# CCM_0009.net
KiCad netlist of a schematic drawn in EAGLE
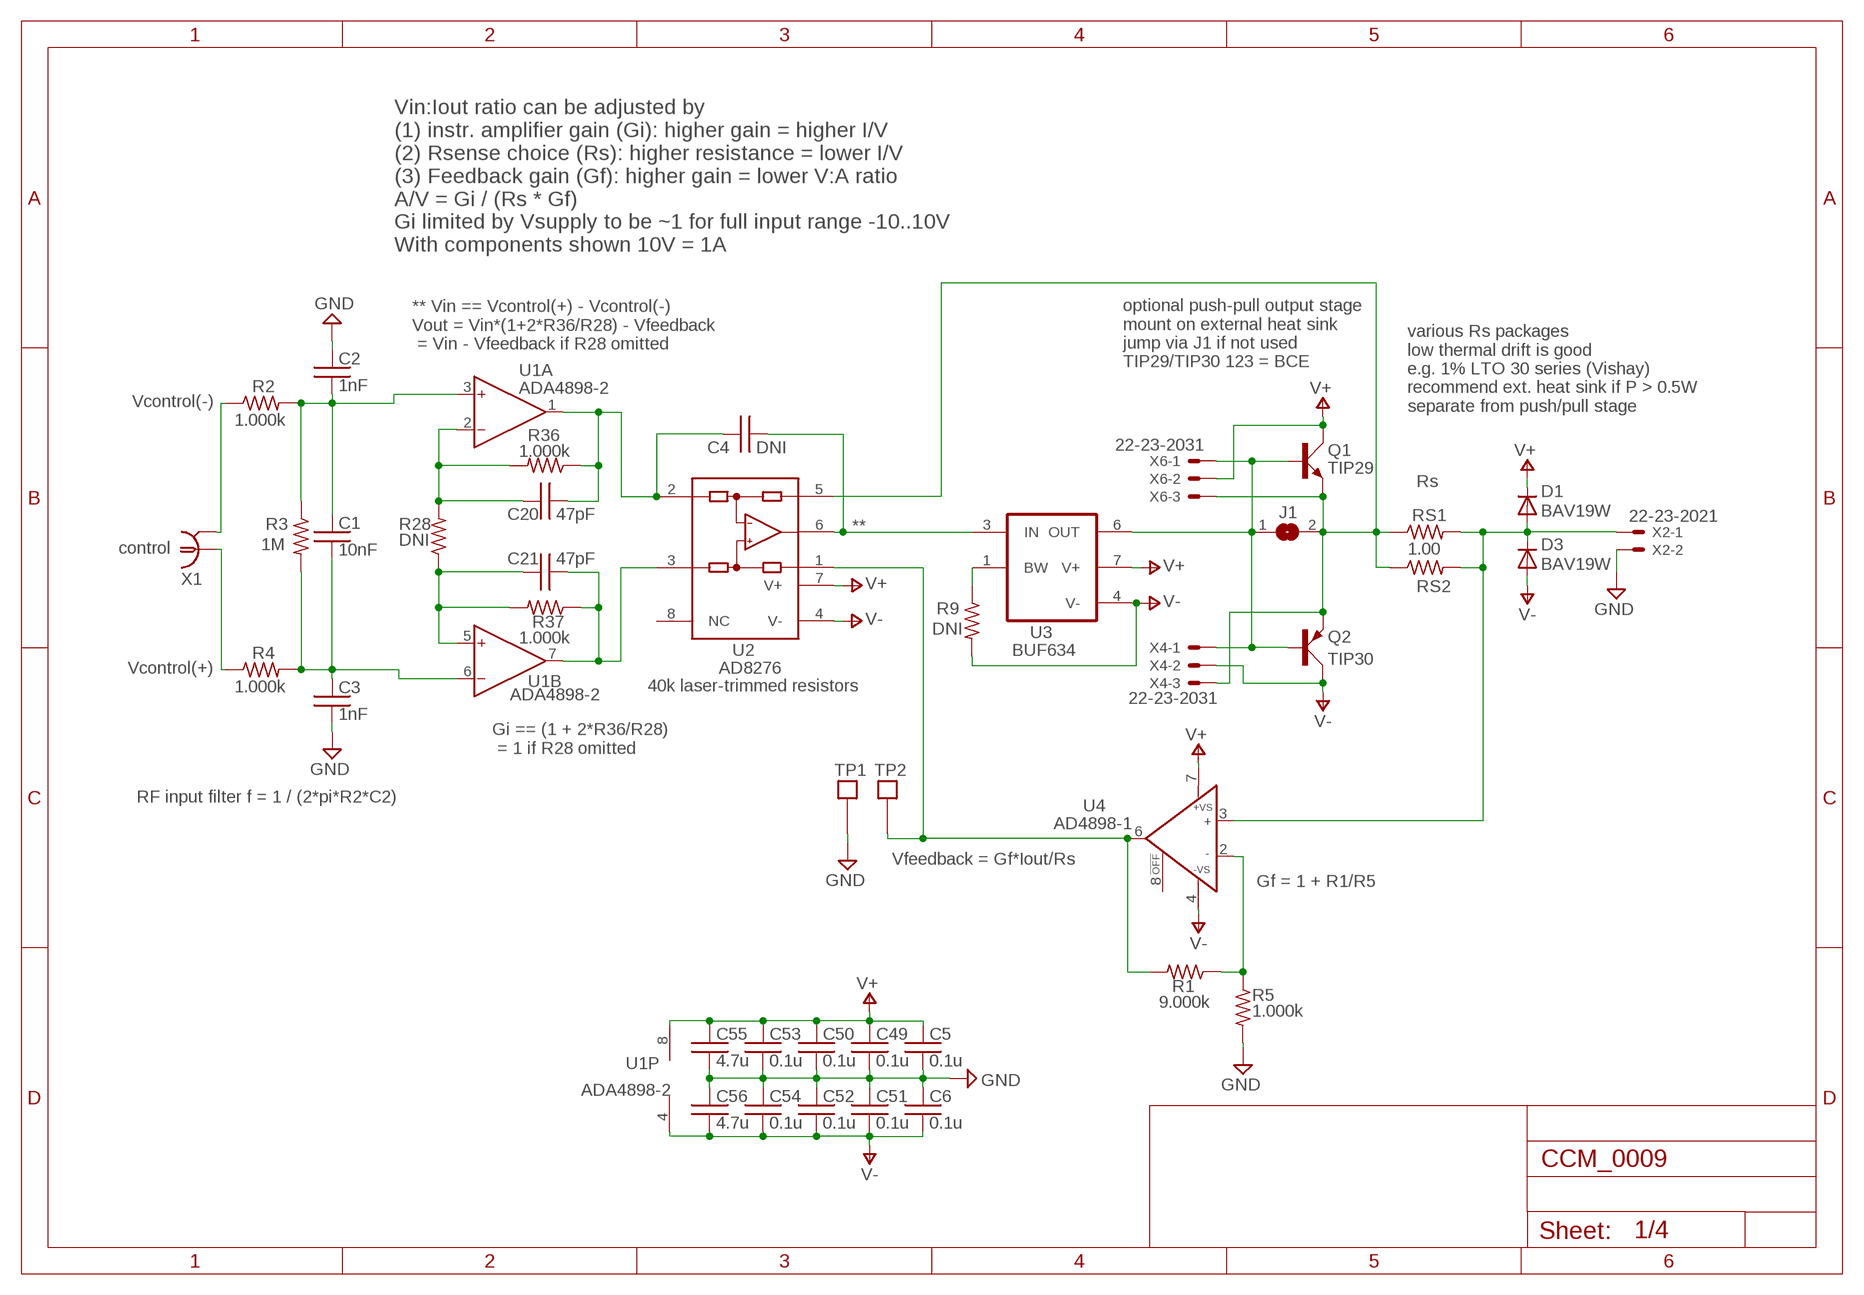
[diagram p0: schematic, sheet 1]
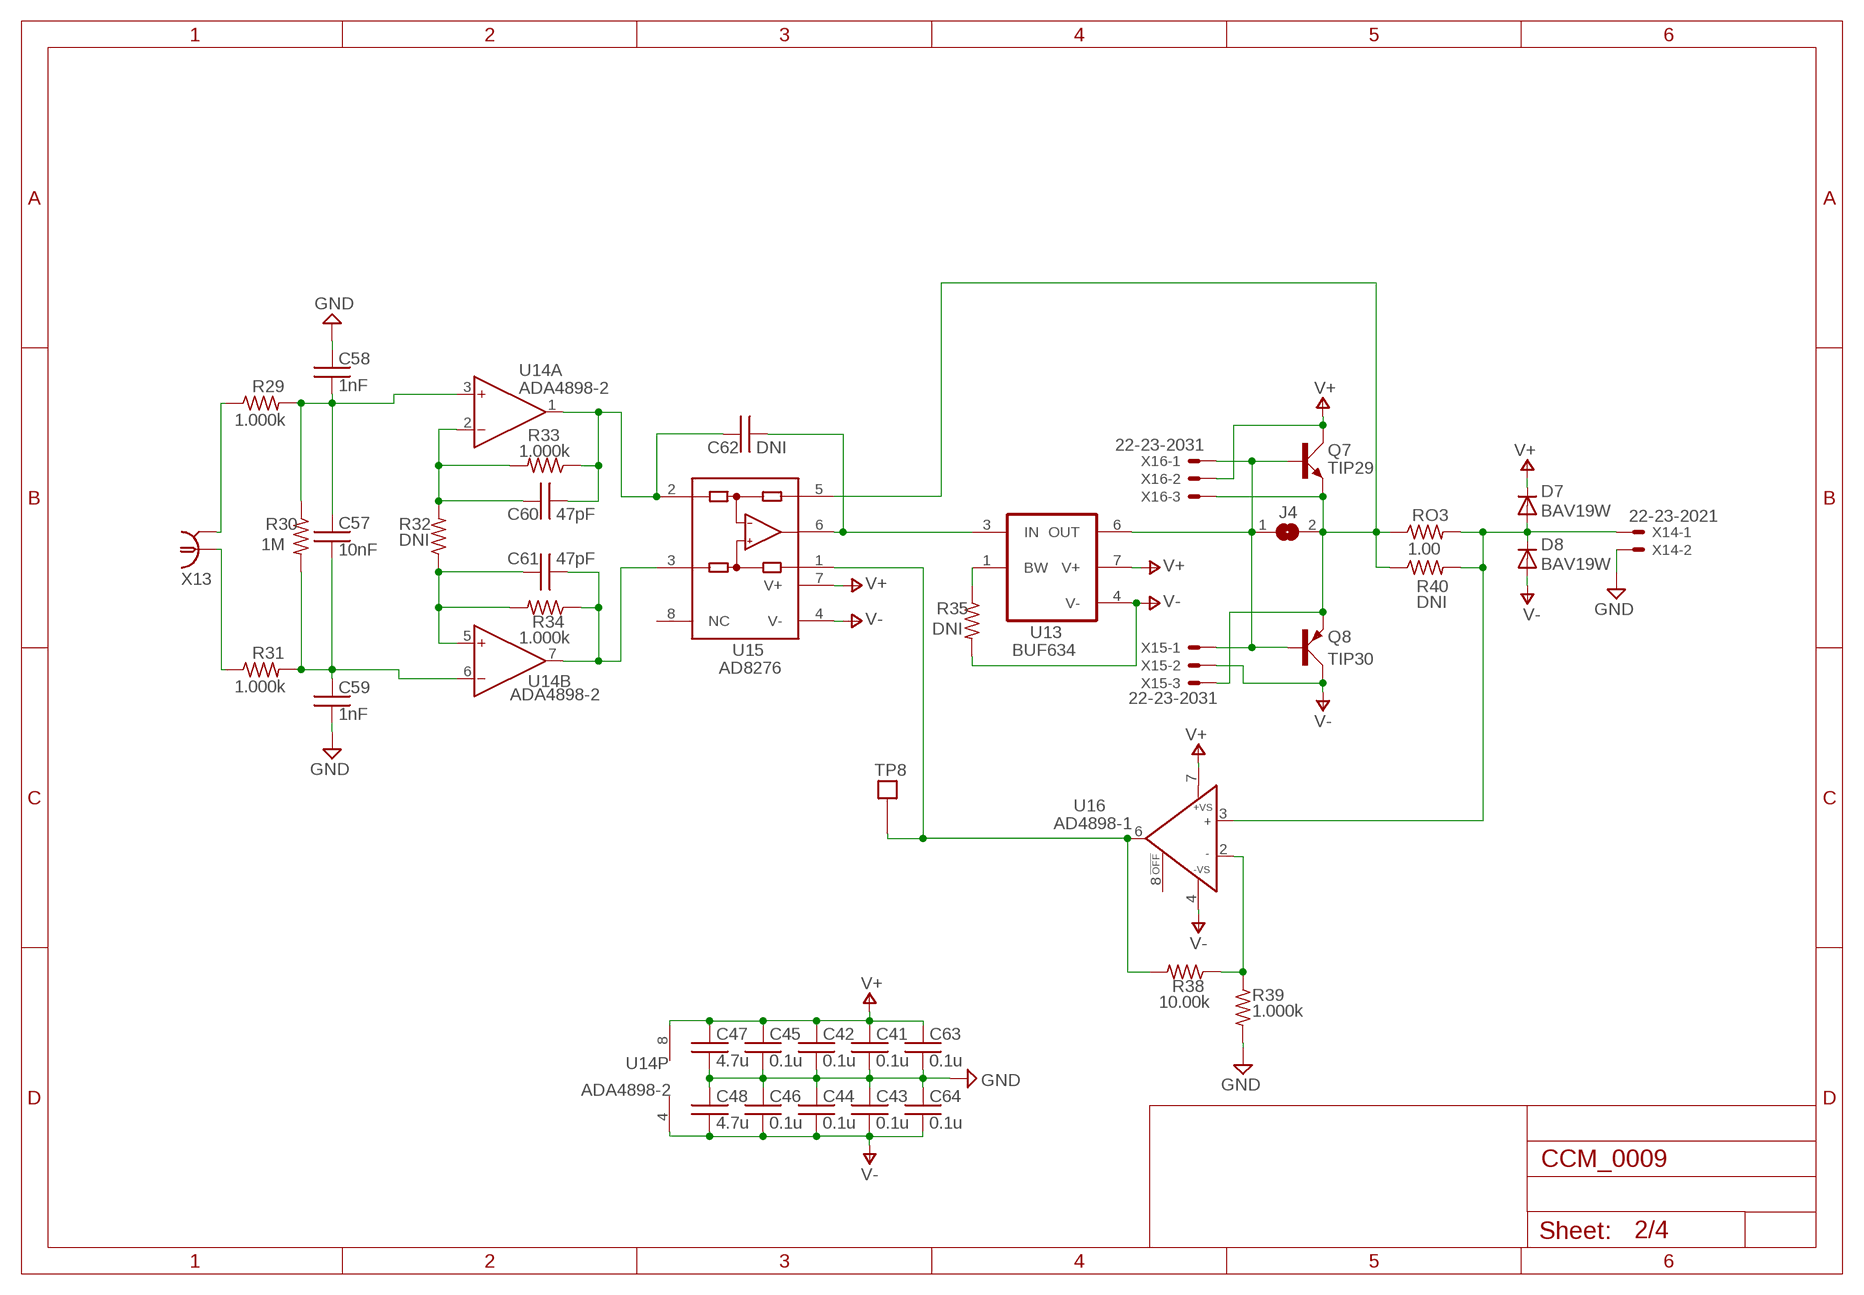
[diagram p1: schematic, sheet 2]
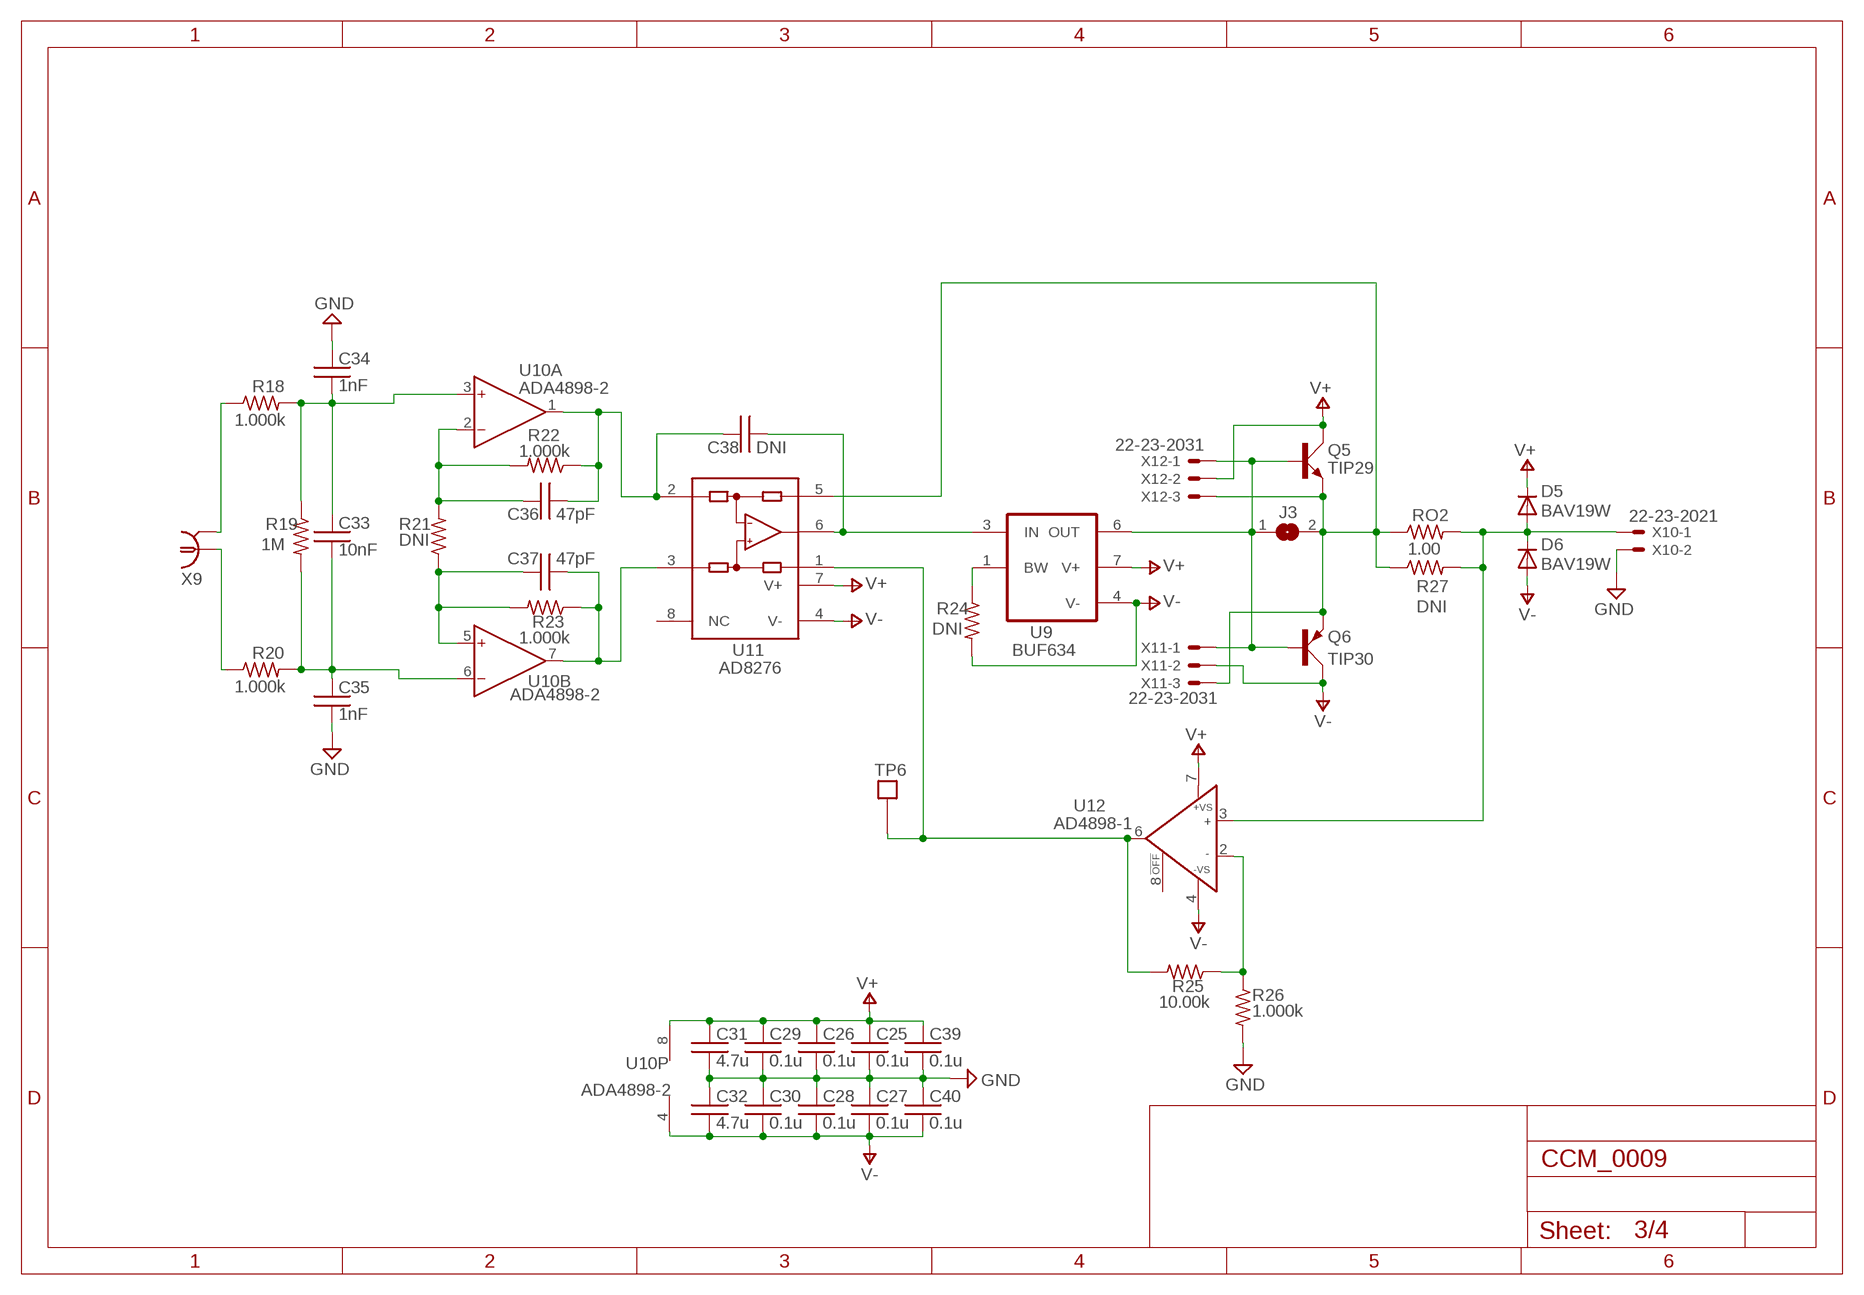
[diagram p2: schematic, sheet 3]
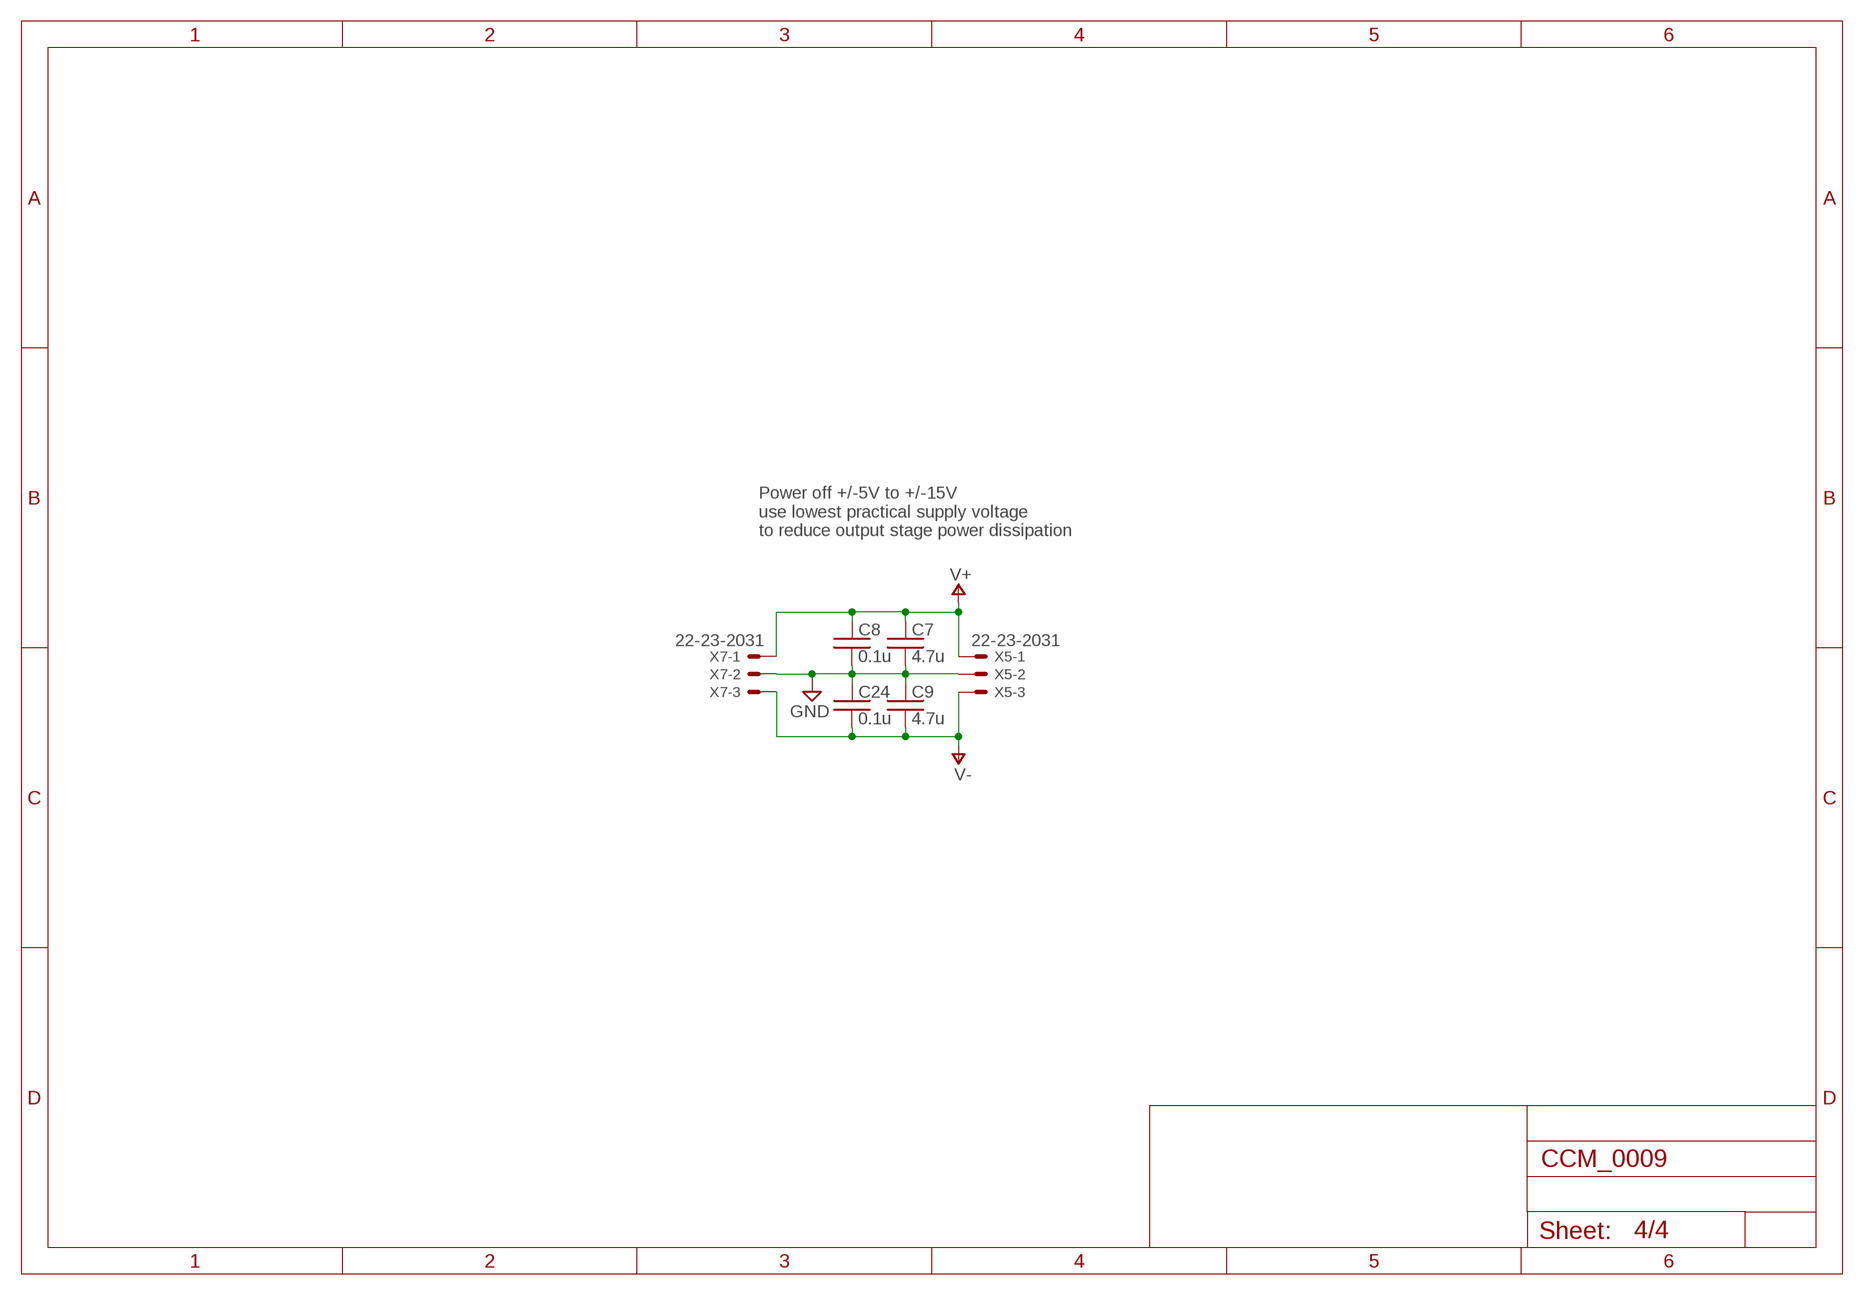
[diagram p3: schematic, sheet 4]

(export (version "E")
  (design (tool "Eeschema 10.0.6"))
  (components
    (comp (ref "C41")
      (value "0.1u")
      (footprint "eagle-import:0603")
      (libsource (lib "eagle-import") (part "C0603"))
    )
    (comp (ref "C42")
      (value "0.1u")
      (footprint "eagle-import:0603")
      (libsource (lib "eagle-import") (part "C0603"))
    )
    (comp (ref "C43")
      (value "0.1u")
      (footprint "eagle-import:0603")
      (libsource (lib "eagle-import") (part "C0603"))
    )
    (comp (ref "C44")
      (value "0.1u")
      (footprint "eagle-import:0603")
      (libsource (lib "eagle-import") (part "C0603"))
    )
    (comp (ref "C45")
      (value "0.1u")
      (footprint "eagle-import:0603")
      (libsource (lib "eagle-import") (part "C0603"))
    )
    (comp (ref "C46")
      (value "0.1u")
      (footprint "eagle-import:0603")
      (libsource (lib "eagle-import") (part "C0603"))
    )
    (comp (ref "C47")
      (value "4.7u")
      (footprint "eagle-import:0603")
      (libsource (lib "eagle-import") (part "C0603"))
    )
    (comp (ref "C48")
      (value "4.7u")
      (footprint "eagle-import:0603")
      (libsource (lib "eagle-import") (part "C0603"))
    )
    (comp (ref "C57")
      (value "10nF")
      (footprint "eagle-import:0603")
      (libsource (lib "eagle-import") (part "C0603"))
    )
    (comp (ref "C58")
      (value "1nF")
      (footprint "eagle-import:0603")
      (libsource (lib "eagle-import") (part "C0603"))
    )
    (comp (ref "C59")
      (value "1nF")
      (footprint "eagle-import:0603")
      (libsource (lib "eagle-import") (part "C0603"))
    )
    (comp (ref "C60")
      (value "47pF")
      (footprint "eagle-import:0603")
      (libsource (lib "eagle-import") (part "C0603"))
    )
    (comp (ref "C61")
      (value "47pF")
      (footprint "eagle-import:0603")
      (libsource (lib "eagle-import") (part "C0603"))
    )
    (comp (ref "C62")
      (value "DNI")
      (footprint "eagle-import:0603")
      (libsource (lib "eagle-import") (part "C0603"))
    )
    (comp (ref "C63")
      (value "0.1u")
      (footprint "eagle-import:0603")
      (libsource (lib "eagle-import") (part "C0603"))
    )
    (comp (ref "C64")
      (value "0.1u")
      (footprint "eagle-import:0603")
      (libsource (lib "eagle-import") (part "C0603"))
    )
    (comp (ref "D7")
      (value "BAV19W")
      (footprint "eagle-import:SOD123")
      (libsource (lib "eagle-import") (part "DIODE-SOD123"))
    )
    (comp (ref "D8")
      (value "BAV19W")
      (footprint "eagle-import:SOD123")
      (libsource (lib "eagle-import") (part "DIODE-SOD123"))
    )
    (comp (ref "J4") (value "SJ") (footprint "eagle-import:SJ") (libsource (lib "eagle-import") (part "SJ")))
    (comp (ref "Q7")
      (value "TIP29")
      (footprint "eagle-import:TO220AV")
      (libsource (lib "eagle-import") (part "TIP41C"))
    )
    (comp (ref "Q8")
      (value "TIP30")
      (footprint "eagle-import:TO220AV")
      (libsource (lib "eagle-import") (part "TIP42C"))
    )
    (comp (ref "R29")
      (value "1.000k")
      (footprint "eagle-import:0603")
      (libsource (lib "eagle-import") (part "R0603"))
    )
    (comp (ref "R30")
      (value "1M")
      (footprint "eagle-import:0603")
      (libsource (lib "eagle-import") (part "R0603"))
    )
    (comp (ref "R31")
      (value "1.000k")
      (footprint "eagle-import:0603")
      (libsource (lib "eagle-import") (part "R0603"))
    )
    (comp (ref "R32")
      (value "DNI")
      (footprint "eagle-import:0603")
      (libsource (lib "eagle-import") (part "R0603"))
    )
    (comp (ref "R33")
      (value "1.000k")
      (footprint "eagle-import:0603")
      (libsource (lib "eagle-import") (part "R0603"))
    )
    (comp (ref "R34")
      (value "1.000k")
      (footprint "eagle-import:0603")
      (libsource (lib "eagle-import") (part "R0603"))
    )
    (comp (ref "R35")
      (value "DNI")
      (footprint "eagle-import:0603")
      (libsource (lib "eagle-import") (part "R0603"))
    )
    (comp (ref "R38")
      (value "10.00k")
      (footprint "eagle-import:0603")
      (libsource (lib "eagle-import") (part "R0603"))
    )
    (comp (ref "R39")
      (value "1.000k")
      (footprint "eagle-import:0603")
      (libsource (lib "eagle-import") (part "R0603"))
    )
    (comp (ref "R40")
      (value "DNI")
      (footprint "eagle-import:2512")
      (libsource (lib "eagle-import") (part "RESISTOR2512"))
    )
    (comp (ref "RO3")
      (value "1.00")
      (footprint "eagle-import:LTO30")
      (libsource (lib "eagle-import") (part "LT030"))
    )
    (comp (ref "TP8")
      (value "TESTPOINT")
      (footprint "eagle-import:TESTPOINT")
      (libsource (lib "eagle-import") (part "TESTPOINT"))
    )
    (comp (ref "U13")
      (value "BUF634")
      (footprint "eagle-import:SO8")
      (libsource (lib "eagle-import") (part "BUF634"))
    )
    (comp (ref "U14")
      (value "ADA4898-2")
      (footprint "eagle-import:SO8")
      (fields (field (name "MF") "ALTERA CORPORATION") (field (name "MPN") "AD8542ARZ-REEL"))
      (libsource (lib "eagle-import") (part "ADA4898-2R"))
    )
    (comp (ref "U15")
      (value "AD8276")
      (footprint "eagle-import:SO8")
      (libsource (lib "eagle-import") (part "AD8276"))
    )
    (comp (ref "U16")
      (value "AD4898-1")
      (footprint "eagle-import:SO8")
      (fields (field (name "MF") "ANALOG DEVICES") (field (name "MPN") "AD744JR"))
      (libsource (lib "eagle-import") (part "ADA4898-1R"))
    )
    (comp (ref "X13")
      (value "1-227161-0")
      (footprint "eagle-import:AMP_227161")
      (fields (field (name "MF") "TYCO ELECTRONICS") (field (name "MPN") "1-227161"))
      (libsource (lib "eagle-import") (part "?2271611--0"))
    )
    (comp (ref "X14")
      (value "22-23-2021")
      (footprint "eagle-import:22-23-2021")
      (fields (field (name "MF") "MOLEX"))
      (libsource (lib "eagle-import") (part "22-23-2021"))
    )
    (comp (ref "X15")
      (value "22-23-2031")
      (footprint "eagle-import:22-23-2031")
      (fields (field (name "MF") "MOLEX"))
      (libsource (lib "eagle-import") (part "con-molex_165_22-23-2031"))
    )
    (comp (ref "X16")
      (value "22-23-2031")
      (footprint "eagle-import:22-23-2031")
      (fields (field (name "MF") "MOLEX"))
      (libsource (lib "eagle-import") (part "con-molex_165_22-23-2031"))
    )
    (comp (ref "C1")
      (value "10nF")
      (footprint "eagle-import:0603")
      (libsource (lib "eagle-import") (part "C0603"))
    )
    (comp (ref "C2")
      (value "1nF")
      (footprint "eagle-import:0603")
      (libsource (lib "eagle-import") (part "C0603"))
    )
    (comp (ref "C3")
      (value "1nF")
      (footprint "eagle-import:0603")
      (libsource (lib "eagle-import") (part "C0603"))
    )
    (comp (ref "C4")
      (value "DNI")
      (footprint "eagle-import:0603")
      (libsource (lib "eagle-import") (part "C0603"))
    )
    (comp (ref "C5")
      (value "0.1u")
      (footprint "eagle-import:0603")
      (libsource (lib "eagle-import") (part "C0603"))
    )
    (comp (ref "C6")
      (value "0.1u")
      (footprint "eagle-import:0603")
      (libsource (lib "eagle-import") (part "C0603"))
    )
    (comp (ref "C20")
      (value "47pF")
      (footprint "eagle-import:0603")
      (libsource (lib "eagle-import") (part "C0603"))
    )
    (comp (ref "C21")
      (value "47pF")
      (footprint "eagle-import:0603")
      (libsource (lib "eagle-import") (part "C0603"))
    )
    (comp (ref "C49")
      (value "0.1u")
      (footprint "eagle-import:0603")
      (libsource (lib "eagle-import") (part "C0603"))
    )
    (comp (ref "C50")
      (value "0.1u")
      (footprint "eagle-import:0603")
      (libsource (lib "eagle-import") (part "C0603"))
    )
    (comp (ref "C51")
      (value "0.1u")
      (footprint "eagle-import:0603")
      (libsource (lib "eagle-import") (part "C0603"))
    )
    (comp (ref "C52")
      (value "0.1u")
      (footprint "eagle-import:0603")
      (libsource (lib "eagle-import") (part "C0603"))
    )
    (comp (ref "C53")
      (value "0.1u")
      (footprint "eagle-import:0603")
      (libsource (lib "eagle-import") (part "C0603"))
    )
    (comp (ref "C54")
      (value "0.1u")
      (footprint "eagle-import:0603")
      (libsource (lib "eagle-import") (part "C0603"))
    )
    (comp (ref "C55")
      (value "4.7u")
      (footprint "eagle-import:0603")
      (libsource (lib "eagle-import") (part "C0603"))
    )
    (comp (ref "C56")
      (value "4.7u")
      (footprint "eagle-import:0603")
      (libsource (lib "eagle-import") (part "C0603"))
    )
    (comp (ref "D1")
      (value "BAV19W")
      (footprint "eagle-import:SOD123")
      (libsource (lib "eagle-import") (part "DIODE-SOD123"))
    )
    (comp (ref "D3")
      (value "BAV19W")
      (footprint "eagle-import:SOD123")
      (libsource (lib "eagle-import") (part "DIODE-SOD123"))
    )
    (comp (ref "J1") (value "SJ") (footprint "eagle-import:SJ") (libsource (lib "eagle-import") (part "SJ")))
    (comp (ref "Q1")
      (value "TIP29")
      (footprint "eagle-import:TO220AV")
      (libsource (lib "eagle-import") (part "TIP41C"))
    )
    (comp (ref "Q2")
      (value "TIP30")
      (footprint "eagle-import:TO220AV")
      (libsource (lib "eagle-import") (part "TIP42C"))
    )
    (comp (ref "R1")
      (value "9.000k")
      (footprint "eagle-import:0603")
      (libsource (lib "eagle-import") (part "R0603"))
    )
    (comp (ref "R2")
      (value "1.000k")
      (footprint "eagle-import:0603")
      (libsource (lib "eagle-import") (part "R0603"))
    )
    (comp (ref "R3")
      (value "1M")
      (footprint "eagle-import:0603")
      (libsource (lib "eagle-import") (part "R0603"))
    )
    (comp (ref "R4")
      (value "1.000k")
      (footprint "eagle-import:0603")
      (libsource (lib "eagle-import") (part "R0603"))
    )
    (comp (ref "R5")
      (value "1.000k")
      (footprint "eagle-import:0603")
      (libsource (lib "eagle-import") (part "R0603"))
    )
    (comp (ref "R9")
      (value "DNI")
      (footprint "eagle-import:0603")
      (libsource (lib "eagle-import") (part "R0603"))
    )
    (comp (ref "R28")
      (value "DNI")
      (footprint "eagle-import:0603")
      (libsource (lib "eagle-import") (part "R0603"))
    )
    (comp (ref "R36")
      (value "1.000k")
      (footprint "eagle-import:0603")
      (libsource (lib "eagle-import") (part "R0603"))
    )
    (comp (ref "R37")
      (value "1.000k")
      (footprint "eagle-import:0603")
      (libsource (lib "eagle-import") (part "R0603"))
    )
    (comp (ref "RS1")
      (value "1.00")
      (footprint "eagle-import:LTO30")
      (libsource (lib "eagle-import") (part "LT030"))
    )
    (comp (ref "RS2")
      (value "DNI")
      (footprint "eagle-import:2512")
      (libsource (lib "eagle-import") (part "RESISTOR2512"))
    )
    (comp (ref "TP1")
      (value "TESTPOINT")
      (footprint "eagle-import:TESTPOINT")
      (libsource (lib "eagle-import") (part "TESTPOINT"))
    )
    (comp (ref "TP2")
      (value "TESTPOINT")
      (footprint "eagle-import:TESTPOINT")
      (libsource (lib "eagle-import") (part "TESTPOINT"))
    )
    (comp (ref "U1")
      (value "ADA4898-2")
      (footprint "eagle-import:SO8")
      (fields (field (name "MF") "ALTERA CORPORATION") (field (name "MPN") "AD8542ARZ-REEL"))
      (libsource (lib "eagle-import") (part "ADA4898-2R"))
    )
    (comp (ref "U2")
      (value "AD8276")
      (footprint "eagle-import:SO8")
      (libsource (lib "eagle-import") (part "AD8276"))
    )
    (comp (ref "U3")
      (value "BUF634")
      (footprint "eagle-import:SO8")
      (libsource (lib "eagle-import") (part "BUF634"))
    )
    (comp (ref "U4")
      (value "AD4898-1")
      (footprint "eagle-import:SO8")
      (fields (field (name "MF") "ANALOG DEVICES") (field (name "MPN") "AD744JR"))
      (libsource (lib "eagle-import") (part "ADA4898-1R"))
    )
    (comp (ref "X1")
      (value "1-227161-0")
      (footprint "eagle-import:AMP_227161")
      (fields (field (name "MF") "TYCO ELECTRONICS") (field (name "MPN") "1-227161"))
      (libsource (lib "eagle-import") (part "?2271611--0"))
    )
    (comp (ref "X2")
      (value "22-23-2021")
      (footprint "eagle-import:22-23-2021")
      (fields (field (name "MF") "MOLEX"))
      (libsource (lib "eagle-import") (part "22-23-2021"))
    )
    (comp (ref "X4")
      (value "22-23-2031")
      (footprint "eagle-import:22-23-2031")
      (fields (field (name "MF") "MOLEX"))
      (libsource (lib "eagle-import") (part "con-molex_165_22-23-2031"))
    )
    (comp (ref "X6")
      (value "22-23-2031")
      (footprint "eagle-import:22-23-2031")
      (fields (field (name "MF") "MOLEX"))
      (libsource (lib "eagle-import") (part "con-molex_165_22-23-2031"))
    )
    (comp (ref "C7")
      (value "4.7u")
      (footprint "eagle-import:0603")
      (libsource (lib "eagle-import") (part "C0603"))
    )
    (comp (ref "C8")
      (value "0.1u")
      (footprint "eagle-import:0603")
      (libsource (lib "eagle-import") (part "C0603"))
    )
    (comp (ref "C9")
      (value "4.7u")
      (footprint "eagle-import:0603")
      (libsource (lib "eagle-import") (part "C0603"))
    )
    (comp (ref "C24")
      (value "0.1u")
      (footprint "eagle-import:0603")
      (libsource (lib "eagle-import") (part "C0603"))
    )
    (comp (ref "X5")
      (value "22-23-2031")
      (footprint "eagle-import:22-23-2031")
      (fields (field (name "MF") "MOLEX"))
      (libsource (lib "eagle-import") (part "22-23-2031"))
    )
    (comp (ref "X7")
      (value "22-23-2031")
      (footprint "eagle-import:22-23-2031")
      (fields (field (name "MF") "MOLEX"))
      (libsource (lib "eagle-import") (part "22-23-2031"))
    )
    (comp (ref "C25")
      (value "0.1u")
      (footprint "eagle-import:0603")
      (libsource (lib "eagle-import") (part "C0603"))
    )
    (comp (ref "C26")
      (value "0.1u")
      (footprint "eagle-import:0603")
      (libsource (lib "eagle-import") (part "C0603"))
    )
    (comp (ref "C27")
      (value "0.1u")
      (footprint "eagle-import:0603")
      (libsource (lib "eagle-import") (part "C0603"))
    )
    (comp (ref "C28")
      (value "0.1u")
      (footprint "eagle-import:0603")
      (libsource (lib "eagle-import") (part "C0603"))
    )
    (comp (ref "C29")
      (value "0.1u")
      (footprint "eagle-import:0603")
      (libsource (lib "eagle-import") (part "C0603"))
    )
    (comp (ref "C30")
      (value "0.1u")
      (footprint "eagle-import:0603")
      (libsource (lib "eagle-import") (part "C0603"))
    )
    (comp (ref "C31")
      (value "4.7u")
      (footprint "eagle-import:0603")
      (libsource (lib "eagle-import") (part "C0603"))
    )
    (comp (ref "C32")
      (value "4.7u")
      (footprint "eagle-import:0603")
      (libsource (lib "eagle-import") (part "C0603"))
    )
    (comp (ref "C33")
      (value "10nF")
      (footprint "eagle-import:0603")
      (libsource (lib "eagle-import") (part "C0603"))
    )
    (comp (ref "C34")
      (value "1nF")
      (footprint "eagle-import:0603")
      (libsource (lib "eagle-import") (part "C0603"))
    )
    (comp (ref "C35")
      (value "1nF")
      (footprint "eagle-import:0603")
      (libsource (lib "eagle-import") (part "C0603"))
    )
    (comp (ref "C36")
      (value "47pF")
      (footprint "eagle-import:0603")
      (libsource (lib "eagle-import") (part "C0603"))
    )
    (comp (ref "C37")
      (value "47pF")
      (footprint "eagle-import:0603")
      (libsource (lib "eagle-import") (part "C0603"))
    )
    (comp (ref "C38")
      (value "DNI")
      (footprint "eagle-import:0603")
      (libsource (lib "eagle-import") (part "C0603"))
    )
    (comp (ref "C39")
      (value "0.1u")
      (footprint "eagle-import:0603")
      (libsource (lib "eagle-import") (part "C0603"))
    )
    (comp (ref "C40")
      (value "0.1u")
      (footprint "eagle-import:0603")
      (libsource (lib "eagle-import") (part "C0603"))
    )
    (comp (ref "D5")
      (value "BAV19W")
      (footprint "eagle-import:SOD123")
      (libsource (lib "eagle-import") (part "DIODE-SOD123"))
    )
    (comp (ref "D6")
      (value "BAV19W")
      (footprint "eagle-import:SOD123")
      (libsource (lib "eagle-import") (part "DIODE-SOD123"))
    )
    (comp (ref "J3") (value "SJ") (footprint "eagle-import:SJ") (libsource (lib "eagle-import") (part "SJ")))
    (comp (ref "Q5")
      (value "TIP29")
      (footprint "eagle-import:TO220AV")
      (libsource (lib "eagle-import") (part "TIP41C"))
    )
    (comp (ref "Q6")
      (value "TIP30")
      (footprint "eagle-import:TO220AV")
      (libsource (lib "eagle-import") (part "TIP42C"))
    )
    (comp (ref "R18")
      (value "1.000k")
      (footprint "eagle-import:0603")
      (libsource (lib "eagle-import") (part "R0603"))
    )
    (comp (ref "R19")
      (value "1M")
      (footprint "eagle-import:0603")
      (libsource (lib "eagle-import") (part "R0603"))
    )
    (comp (ref "R20")
      (value "1.000k")
      (footprint "eagle-import:0603")
      (libsource (lib "eagle-import") (part "R0603"))
    )
    (comp (ref "R21")
      (value "DNI")
      (footprint "eagle-import:0603")
      (libsource (lib "eagle-import") (part "R0603"))
    )
    (comp (ref "R22")
      (value "1.000k")
      (footprint "eagle-import:0603")
      (libsource (lib "eagle-import") (part "R0603"))
    )
    (comp (ref "R23")
      (value "1.000k")
      (footprint "eagle-import:0603")
      (libsource (lib "eagle-import") (part "R0603"))
    )
    (comp (ref "R24")
      (value "DNI")
      (footprint "eagle-import:0603")
      (libsource (lib "eagle-import") (part "R0603"))
    )
    (comp (ref "R25")
      (value "10.00k")
      (footprint "eagle-import:0603")
      (libsource (lib "eagle-import") (part "R0603"))
    )
    (comp (ref "R26")
      (value "1.000k")
      (footprint "eagle-import:0603")
      (libsource (lib "eagle-import") (part "R0603"))
    )
    (comp (ref "R27")
      (value "DNI")
      (footprint "eagle-import:2512")
      (libsource (lib "eagle-import") (part "RESISTOR2512"))
    )
    (comp (ref "RO2")
      (value "1.00")
      (footprint "eagle-import:LTO30")
      (libsource (lib "eagle-import") (part "LT030"))
    )
    (comp (ref "TP6")
      (value "TESTPOINT")
      (footprint "eagle-import:TESTPOINT")
      (libsource (lib "eagle-import") (part "TESTPOINT"))
    )
    (comp (ref "U9")
      (value "BUF634")
      (footprint "eagle-import:SO8")
      (libsource (lib "eagle-import") (part "BUF634"))
    )
    (comp (ref "U10")
      (value "ADA4898-2")
      (footprint "eagle-import:SO8")
      (fields (field (name "MF") "ALTERA CORPORATION") (field (name "MPN") "AD8542ARZ-REEL"))
      (libsource (lib "eagle-import") (part "ADA4898-2R"))
    )
    (comp (ref "U11")
      (value "AD8276")
      (footprint "eagle-import:SO8")
      (libsource (lib "eagle-import") (part "AD8276"))
    )
    (comp (ref "U12")
      (value "AD4898-1")
      (footprint "eagle-import:SO8")
      (fields (field (name "MF") "ANALOG DEVICES") (field (name "MPN") "AD744JR"))
      (libsource (lib "eagle-import") (part "ADA4898-1R"))
    )
    (comp (ref "X9")
      (value "1-227161-0")
      (footprint "eagle-import:AMP_227161")
      (fields (field (name "MF") "TYCO ELECTRONICS") (field (name "MPN") "1-227161"))
      (libsource (lib "eagle-import") (part "?2271611--0"))
    )
    (comp (ref "X10")
      (value "22-23-2021")
      (footprint "eagle-import:22-23-2021")
      (fields (field (name "MF") "MOLEX"))
      (libsource (lib "eagle-import") (part "22-23-2021"))
    )
    (comp (ref "X11")
      (value "22-23-2031")
      (footprint "eagle-import:22-23-2031")
      (fields (field (name "MF") "MOLEX"))
      (libsource (lib "eagle-import") (part "con-molex_165_22-23-2031"))
    )
    (comp (ref "X12")
      (value "22-23-2031")
      (footprint "eagle-import:22-23-2031")
      (fields (field (name "MF") "MOLEX"))
      (libsource (lib "eagle-import") (part "con-molex_165_22-23-2031"))
    )
  )
  (nets
    (net (code "1") (name "GND") (class "Default")
      (node (ref "C2") (pin "1") (pinfunction "1_1") (pintype "passive"))
      (node (ref "C24") (pin "1") (pinfunction "1_1") (pintype "passive"))
      (node (ref "C25") (pin "2") (pinfunction "2_2") (pintype "passive"))
      (node (ref "C26") (pin "2") (pinfunction "2_2") (pintype "passive"))
      (node (ref "C27") (pin "1") (pinfunction "1_1") (pintype "passive"))
      (node (ref "C28") (pin "1") (pinfunction "1_1") (pintype "passive"))
      (node (ref "C29") (pin "2") (pinfunction "2_2") (pintype "passive"))
      (node (ref "C3") (pin "2") (pinfunction "2_2") (pintype "passive"))
      (node (ref "C30") (pin "1") (pinfunction "1_1") (pintype "passive"))
      (node (ref "C31") (pin "2") (pinfunction "2_2") (pintype "passive"))
      (node (ref "C32") (pin "1") (pinfunction "1_1") (pintype "passive"))
      (node (ref "C34") (pin "1") (pinfunction "1_1") (pintype "passive"))
      (node (ref "C35") (pin "2") (pinfunction "2_2") (pintype "passive"))
      (node (ref "C39") (pin "2") (pinfunction "2_2") (pintype "passive"))
      (node (ref "C40") (pin "1") (pinfunction "1_1") (pintype "passive"))
      (node (ref "C41") (pin "2") (pinfunction "2_2") (pintype "passive"))
      (node (ref "C42") (pin "2") (pinfunction "2_2") (pintype "passive"))
      (node (ref "C43") (pin "1") (pinfunction "1_1") (pintype "passive"))
      (node (ref "C44") (pin "1") (pinfunction "1_1") (pintype "passive"))
      (node (ref "C45") (pin "2") (pinfunction "2_2") (pintype "passive"))
      (node (ref "C46") (pin "1") (pinfunction "1_1") (pintype "passive"))
      (node (ref "C47") (pin "2") (pinfunction "2_2") (pintype "passive"))
      (node (ref "C48") (pin "1") (pinfunction "1_1") (pintype "passive"))
      (node (ref "C49") (pin "2") (pinfunction "2_2") (pintype "passive"))
      (node (ref "C5") (pin "2") (pinfunction "2_2") (pintype "passive"))
      (node (ref "C50") (pin "2") (pinfunction "2_2") (pintype "passive"))
      (node (ref "C51") (pin "1") (pinfunction "1_1") (pintype "passive"))
      (node (ref "C52") (pin "1") (pinfunction "1_1") (pintype "passive"))
      (node (ref "C53") (pin "2") (pinfunction "2_2") (pintype "passive"))
      (node (ref "C54") (pin "1") (pinfunction "1_1") (pintype "passive"))
      (node (ref "C55") (pin "2") (pinfunction "2_2") (pintype "passive"))
      (node (ref "C56") (pin "1") (pinfunction "1_1") (pintype "passive"))
      (node (ref "C58") (pin "1") (pinfunction "1_1") (pintype "passive"))
      (node (ref "C59") (pin "2") (pinfunction "2_2") (pintype "passive"))
      (node (ref "C6") (pin "1") (pinfunction "1_1") (pintype "passive"))
      (node (ref "C63") (pin "2") (pinfunction "2_2") (pintype "passive"))
      (node (ref "C64") (pin "1") (pinfunction "1_1") (pintype "passive"))
      (node (ref "C7") (pin "2") (pinfunction "2_2") (pintype "passive"))
      (node (ref "C8") (pin "2") (pinfunction "2_2") (pintype "passive"))
      (node (ref "C9") (pin "1") (pinfunction "1_1") (pintype "passive"))
      (node (ref "R26") (pin "2") (pinfunction "2_2") (pintype "passive"))
      (node (ref "R39") (pin "2") (pinfunction "2_2") (pintype "passive"))
      (node (ref "R5") (pin "2") (pinfunction "2_2") (pintype "passive"))
      (node (ref "TP1") (pin "P$1") (pinfunction "P$1_P$1") (pintype "bidirectional"))
      (node (ref "X10") (pin "2") (pinfunction "S_2") (pintype "passive"))
      (node (ref "X14") (pin "2") (pinfunction "S_2") (pintype "passive"))
      (node (ref "X2") (pin "2") (pinfunction "S_2") (pintype "passive"))
      (node (ref "X5") (pin "2") (pinfunction "S_2") (pintype "passive"))
      (node (ref "X7") (pin "2") (pinfunction "S_2") (pintype "passive"))
    )
    (net (code "2") (name "Net-(R2-Pad1)") (class "Default")
      (node (ref "R2") (pin "1") (pinfunction "1_1") (pintype "passive"))
      (node (ref "X1") (pin "2") (pinfunction "2_2") (pintype "passive"))
    )
    (net (code "3") (name "Net-(R4-Pad1)") (class "Default")
      (node (ref "R4") (pin "1") (pinfunction "1_1") (pintype "passive"))
      (node (ref "X1") (pin "1") (pinfunction "1_1") (pintype "passive"))
    )
    (net (code "4") (name "Net-(R18-Pad1)") (class "Default")
      (node (ref "R18") (pin "1") (pinfunction "1_1") (pintype "passive"))
      (node (ref "X9") (pin "2") (pinfunction "2_2") (pintype "passive"))
    )
    (net (code "5") (name "Net-(R20-Pad1)") (class "Default")
      (node (ref "R20") (pin "1") (pinfunction "1_1") (pintype "passive"))
      (node (ref "X9") (pin "1") (pinfunction "1_1") (pintype "passive"))
    )
    (net (code "6") (name "Net-(R29-Pad1)") (class "Default")
      (node (ref "R29") (pin "1") (pinfunction "1_1") (pintype "passive"))
      (node (ref "X13") (pin "2") (pinfunction "2_2") (pintype "passive"))
    )
    (net (code "7") (name "Net-(R31-Pad1)") (class "Default")
      (node (ref "R31") (pin "1") (pinfunction "1_1") (pintype "passive"))
      (node (ref "X13") (pin "1") (pinfunction "1_1") (pintype "passive"))
    )
    (net (code "8") (name "Net-(RO2-1)") (class "Default")
      (node (ref "J3") (pin "2") (pinfunction "2_2") (pintype "passive"))
      (node (ref "Q5") (pin "E") (pinfunction "E_E") (pintype "passive"))
      (node (ref "Q6") (pin "E") (pinfunction "E_E") (pintype "passive"))
      (node (ref "R27") (pin "1") (pinfunction "1_1") (pintype "passive"))
      (node (ref "RO2") (pin "P$1") (pinfunction "1_P$1") (pintype "passive"))
      (node (ref "U11") (pin "5") (pinfunction "SENSE_5") (pintype "passive"))
      (node (ref "X11") (pin "3") (pinfunction "S_3") (pintype "passive"))
      (node (ref "X12") (pin "3") (pinfunction "S_3") (pintype "passive"))
    )
    (net (code "9") (name "Net-(RO2-2)") (class "Default")
      (node (ref "D5") (pin "A") (pinfunction "A_A") (pintype "passive"))
      (node (ref "D6") (pin "C") (pinfunction "C_C") (pintype "passive"))
      (node (ref "R27") (pin "2") (pinfunction "2_2") (pintype "passive"))
      (node (ref "RO2") (pin "P$2") (pinfunction "2_P$2") (pintype "passive"))
      (node (ref "U12") (pin "3") (pinfunction "IN+_3") (pintype "input"))
      (node (ref "X10") (pin "1") (pinfunction "S_1") (pintype "passive"))
    )
    (net (code "10") (name "Net-(RO3-1)") (class "Default")
      (node (ref "J4") (pin "2") (pinfunction "2_2") (pintype "passive"))
      (node (ref "Q7") (pin "E") (pinfunction "E_E") (pintype "passive"))
      (node (ref "Q8") (pin "E") (pinfunction "E_E") (pintype "passive"))
      (node (ref "R40") (pin "1") (pinfunction "1_1") (pintype "passive"))
      (node (ref "RO3") (pin "P$1") (pinfunction "1_P$1") (pintype "passive"))
      (node (ref "U15") (pin "5") (pinfunction "SENSE_5") (pintype "passive"))
      (node (ref "X15") (pin "3") (pinfunction "S_3") (pintype "passive"))
      (node (ref "X16") (pin "3") (pinfunction "S_3") (pintype "passive"))
    )
    (net (code "11") (name "Net-(RO3-2)") (class "Default")
      (node (ref "D7") (pin "A") (pinfunction "A_A") (pintype "passive"))
      (node (ref "D8") (pin "C") (pinfunction "C_C") (pintype "passive"))
      (node (ref "R40") (pin "2") (pinfunction "2_2") (pintype "passive"))
      (node (ref "RO3") (pin "P$2") (pinfunction "2_P$2") (pintype "passive"))
      (node (ref "U16") (pin "3") (pinfunction "IN+_3") (pintype "input"))
      (node (ref "X14") (pin "1") (pinfunction "S_1") (pintype "passive"))
    )
    (net (code "12") (name "Net-(RS1-1)") (class "Default")
      (node (ref "J1") (pin "2") (pinfunction "2_2") (pintype "passive"))
      (node (ref "Q1") (pin "E") (pinfunction "E_E") (pintype "passive"))
      (node (ref "Q2") (pin "E") (pinfunction "E_E") (pintype "passive"))
      (node (ref "RS1") (pin "P$1") (pinfunction "1_P$1") (pintype "passive"))
      (node (ref "RS2") (pin "1") (pinfunction "1_1") (pintype "passive"))
      (node (ref "U2") (pin "5") (pinfunction "SENSE_5") (pintype "passive"))
      (node (ref "X4") (pin "3") (pinfunction "S_3") (pintype "passive"))
      (node (ref "X6") (pin "3") (pinfunction "S_3") (pintype "passive"))
    )
    (net (code "13") (name "Net-(RS1-2)") (class "Default")
      (node (ref "D1") (pin "A") (pinfunction "A_A") (pintype "passive"))
      (node (ref "D3") (pin "C") (pinfunction "C_C") (pintype "passive"))
      (node (ref "RS1") (pin "P$2") (pinfunction "2_P$2") (pintype "passive"))
      (node (ref "RS2") (pin "2") (pinfunction "2_2") (pintype "passive"))
      (node (ref "U4") (pin "3") (pinfunction "IN+_3") (pintype "input"))
      (node (ref "X2") (pin "1") (pinfunction "S_1") (pintype "passive"))
    )
    (net (code "14") (name "Net-(U1A-IN+)") (class "Default")
      (node (ref "C1") (pin "1") (pinfunction "1_1") (pintype "passive"))
      (node (ref "C2") (pin "2") (pinfunction "2_2") (pintype "passive"))
      (node (ref "R2") (pin "2") (pinfunction "2_2") (pintype "passive"))
      (node (ref "R3") (pin "1") (pinfunction "1_1") (pintype "passive"))
      (node (ref "U1") (pin "3") (pinfunction "IN+_3") (pintype "input"))
    )
    (net (code "15") (name "Net-(U1A-IN-)") (class "Default")
      (node (ref "C20") (pin "1") (pinfunction "1_1") (pintype "passive"))
      (node (ref "R28") (pin "2") (pinfunction "2_2") (pintype "passive"))
      (node (ref "R36") (pin "2") (pinfunction "2_2") (pintype "passive"))
      (node (ref "U1") (pin "2") (pinfunction "IN-_2") (pintype "input"))
    )
    (net (code "16") (name "Net-(U1A-OUT)") (class "Default")
      (node (ref "C20") (pin "2") (pinfunction "2_2") (pintype "passive"))
      (node (ref "C4") (pin "1") (pinfunction "1_1") (pintype "passive"))
      (node (ref "R36") (pin "1") (pinfunction "1_1") (pintype "passive"))
      (node (ref "U1") (pin "1") (pinfunction "OUT_1") (pintype "output"))
      (node (ref "U2") (pin "2") (pinfunction "-IN_2") (pintype "input"))
    )
    (net (code "17") (name "Net-(U1B-IN+)") (class "Default")
      (node (ref "C21") (pin "1") (pinfunction "1_1") (pintype "passive"))
      (node (ref "R28") (pin "1") (pinfunction "1_1") (pintype "passive"))
      (node (ref "R37") (pin "2") (pinfunction "2_2") (pintype "passive"))
      (node (ref "U1") (pin "5") (pinfunction "IN+_5") (pintype "input"))
    )
    (net (code "18") (name "Net-(U1B-IN-)") (class "Default")
      (node (ref "C1") (pin "2") (pinfunction "2_2") (pintype "passive"))
      (node (ref "C3") (pin "1") (pinfunction "1_1") (pintype "passive"))
      (node (ref "R3") (pin "2") (pinfunction "2_2") (pintype "passive"))
      (node (ref "R4") (pin "2") (pinfunction "2_2") (pintype "passive"))
      (node (ref "U1") (pin "6") (pinfunction "IN-_6") (pintype "input"))
    )
    (net (code "19") (name "Net-(U1B-OUT)") (class "Default")
      (node (ref "C21") (pin "2") (pinfunction "2_2") (pintype "passive"))
      (node (ref "R37") (pin "1") (pinfunction "1_1") (pintype "passive"))
      (node (ref "U1") (pin "7") (pinfunction "OUT_7") (pintype "output"))
      (node (ref "U2") (pin "3") (pinfunction "+IN_3") (pintype "input"))
    )
    (net (code "20") (name "Net-(U2-OUT)") (class "Default")
      (node (ref "C4") (pin "2") (pinfunction "2_2") (pintype "passive"))
      (node (ref "U2") (pin "6") (pinfunction "OUT_6") (pintype "output"))
      (node (ref "U3") (pin "3") (pinfunction "IN_3") (pintype "input"))
    )
    (net (code "21") (name "Net-(U2-REF)") (class "Default")
      (node (ref "R1") (pin "2") (pinfunction "2_2") (pintype "passive"))
      (node (ref "TP2") (pin "P$1") (pinfunction "P$1_P$1") (pintype "bidirectional"))
      (node (ref "U2") (pin "1") (pinfunction "REF_1") (pintype "passive"))
      (node (ref "U4") (pin "6") (pinfunction "OUT_6") (pintype "output"))
    )
    (net (code "22") (name "Net-(U3-BW)") (class "Default")
      (node (ref "R9") (pin "1") (pinfunction "1_1") (pintype "passive"))
      (node (ref "U3") (pin "1") (pinfunction "BW_1") (pintype "passive"))
    )
    (net (code "23") (name "Net-(U3-OUT)") (class "Default")
      (node (ref "J1") (pin "1") (pinfunction "1_1") (pintype "passive"))
      (node (ref "Q1") (pin "B") (pinfunction "B_B") (pintype "passive"))
      (node (ref "Q2") (pin "B") (pinfunction "B_B") (pintype "passive"))
      (node (ref "U3") (pin "6") (pinfunction "OUT_6") (pintype "output"))
      (node (ref "X4") (pin "1") (pinfunction "S_1") (pintype "passive"))
      (node (ref "X6") (pin "1") (pinfunction "S_1") (pintype "passive"))
    )
    (net (code "24") (name "Net-(U4-IN-)") (class "Default")
      (node (ref "R1") (pin "1") (pinfunction "1_1") (pintype "passive"))
      (node (ref "R5") (pin "1") (pinfunction "1_1") (pintype "passive"))
      (node (ref "U4") (pin "2") (pinfunction "IN-_2") (pintype "input"))
    )
    (net (code "25") (name "Net-(U9-BW)") (class "Default")
      (node (ref "R24") (pin "1") (pinfunction "1_1") (pintype "passive"))
      (node (ref "U9") (pin "1") (pinfunction "BW_1") (pintype "passive"))
    )
    (net (code "26") (name "Net-(U9-OUT)") (class "Default")
      (node (ref "J3") (pin "1") (pinfunction "1_1") (pintype "passive"))
      (node (ref "Q5") (pin "B") (pinfunction "B_B") (pintype "passive"))
      (node (ref "Q6") (pin "B") (pinfunction "B_B") (pintype "passive"))
      (node (ref "U9") (pin "6") (pinfunction "OUT_6") (pintype "output"))
      (node (ref "X11") (pin "1") (pinfunction "S_1") (pintype "passive"))
      (node (ref "X12") (pin "1") (pinfunction "S_1") (pintype "passive"))
    )
    (net (code "27") (name "Net-(U10A-IN+)") (class "Default")
      (node (ref "C33") (pin "1") (pinfunction "1_1") (pintype "passive"))
      (node (ref "C34") (pin "2") (pinfunction "2_2") (pintype "passive"))
      (node (ref "R18") (pin "2") (pinfunction "2_2") (pintype "passive"))
      (node (ref "R19") (pin "1") (pinfunction "1_1") (pintype "passive"))
      (node (ref "U10") (pin "3") (pinfunction "IN+_3") (pintype "input"))
    )
    (net (code "28") (name "Net-(U10A-IN-)") (class "Default")
      (node (ref "C36") (pin "1") (pinfunction "1_1") (pintype "passive"))
      (node (ref "R21") (pin "2") (pinfunction "2_2") (pintype "passive"))
      (node (ref "R22") (pin "2") (pinfunction "2_2") (pintype "passive"))
      (node (ref "U10") (pin "2") (pinfunction "IN-_2") (pintype "input"))
    )
    (net (code "29") (name "Net-(U10A-OUT)") (class "Default")
      (node (ref "C36") (pin "2") (pinfunction "2_2") (pintype "passive"))
      (node (ref "C38") (pin "1") (pinfunction "1_1") (pintype "passive"))
      (node (ref "R22") (pin "1") (pinfunction "1_1") (pintype "passive"))
      (node (ref "U10") (pin "1") (pinfunction "OUT_1") (pintype "output"))
      (node (ref "U11") (pin "2") (pinfunction "-IN_2") (pintype "input"))
    )
    (net (code "30") (name "Net-(U10B-IN+)") (class "Default")
      (node (ref "C37") (pin "1") (pinfunction "1_1") (pintype "passive"))
      (node (ref "R21") (pin "1") (pinfunction "1_1") (pintype "passive"))
      (node (ref "R23") (pin "2") (pinfunction "2_2") (pintype "passive"))
      (node (ref "U10") (pin "5") (pinfunction "IN+_5") (pintype "input"))
    )
    (net (code "31") (name "Net-(U10B-IN-)") (class "Default")
      (node (ref "C33") (pin "2") (pinfunction "2_2") (pintype "passive"))
      (node (ref "C35") (pin "1") (pinfunction "1_1") (pintype "passive"))
      (node (ref "R19") (pin "2") (pinfunction "2_2") (pintype "passive"))
      (node (ref "R20") (pin "2") (pinfunction "2_2") (pintype "passive"))
      (node (ref "U10") (pin "6") (pinfunction "IN-_6") (pintype "input"))
    )
    (net (code "32") (name "Net-(U10B-OUT)") (class "Default")
      (node (ref "C37") (pin "2") (pinfunction "2_2") (pintype "passive"))
      (node (ref "R23") (pin "1") (pinfunction "1_1") (pintype "passive"))
      (node (ref "U10") (pin "7") (pinfunction "OUT_7") (pintype "output"))
      (node (ref "U11") (pin "3") (pinfunction "+IN_3") (pintype "input"))
    )
    (net (code "33") (name "Net-(U11-OUT)") (class "Default")
      (node (ref "C38") (pin "2") (pinfunction "2_2") (pintype "passive"))
      (node (ref "U11") (pin "6") (pinfunction "OUT_6") (pintype "output"))
      (node (ref "U9") (pin "3") (pinfunction "IN_3") (pintype "input"))
    )
    (net (code "34") (name "Net-(U11-REF)") (class "Default")
      (node (ref "R25") (pin "2") (pinfunction "2_2") (pintype "passive"))
      (node (ref "TP6") (pin "P$1") (pinfunction "P$1_P$1") (pintype "bidirectional"))
      (node (ref "U11") (pin "1") (pinfunction "REF_1") (pintype "passive"))
      (node (ref "U12") (pin "6") (pinfunction "OUT_6") (pintype "output"))
    )
    (net (code "35") (name "Net-(U12-IN-)") (class "Default")
      (node (ref "R25") (pin "1") (pinfunction "1_1") (pintype "passive"))
      (node (ref "R26") (pin "1") (pinfunction "1_1") (pintype "passive"))
      (node (ref "U12") (pin "2") (pinfunction "IN-_2") (pintype "input"))
    )
    (net (code "36") (name "Net-(U13-BW)") (class "Default")
      (node (ref "R35") (pin "1") (pinfunction "1_1") (pintype "passive"))
      (node (ref "U13") (pin "1") (pinfunction "BW_1") (pintype "passive"))
    )
    (net (code "37") (name "Net-(U13-IN)") (class "Default")
      (node (ref "C62") (pin "2") (pinfunction "2_2") (pintype "passive"))
      (node (ref "U13") (pin "3") (pinfunction "IN_3") (pintype "input"))
      (node (ref "U15") (pin "6") (pinfunction "OUT_6") (pintype "output"))
    )
    (net (code "38") (name "Net-(U13-OUT)") (class "Default")
      (node (ref "J4") (pin "1") (pinfunction "1_1") (pintype "passive"))
      (node (ref "Q7") (pin "B") (pinfunction "B_B") (pintype "passive"))
      (node (ref "Q8") (pin "B") (pinfunction "B_B") (pintype "passive"))
      (node (ref "U13") (pin "6") (pinfunction "OUT_6") (pintype "output"))
      (node (ref "X15") (pin "1") (pinfunction "S_1") (pintype "passive"))
      (node (ref "X16") (pin "1") (pinfunction "S_1") (pintype "passive"))
    )
    (net (code "39") (name "Net-(U14A-IN+)") (class "Default")
      (node (ref "C57") (pin "1") (pinfunction "1_1") (pintype "passive"))
      (node (ref "C58") (pin "2") (pinfunction "2_2") (pintype "passive"))
      (node (ref "R29") (pin "2") (pinfunction "2_2") (pintype "passive"))
      (node (ref "R30") (pin "1") (pinfunction "1_1") (pintype "passive"))
      (node (ref "U14") (pin "3") (pinfunction "IN+_3") (pintype "input"))
    )
    (net (code "40") (name "Net-(U14A-IN-)") (class "Default")
      (node (ref "C60") (pin "1") (pinfunction "1_1") (pintype "passive"))
      (node (ref "R32") (pin "2") (pinfunction "2_2") (pintype "passive"))
      (node (ref "R33") (pin "2") (pinfunction "2_2") (pintype "passive"))
      (node (ref "U14") (pin "2") (pinfunction "IN-_2") (pintype "input"))
    )
    (net (code "41") (name "Net-(U14A-OUT)") (class "Default")
      (node (ref "C60") (pin "2") (pinfunction "2_2") (pintype "passive"))
      (node (ref "C62") (pin "1") (pinfunction "1_1") (pintype "passive"))
      (node (ref "R33") (pin "1") (pinfunction "1_1") (pintype "passive"))
      (node (ref "U14") (pin "1") (pinfunction "OUT_1") (pintype "output"))
      (node (ref "U15") (pin "2") (pinfunction "-IN_2") (pintype "input"))
    )
    (net (code "42") (name "Net-(U14B-IN+)") (class "Default")
      (node (ref "C61") (pin "1") (pinfunction "1_1") (pintype "passive"))
      (node (ref "R32") (pin "1") (pinfunction "1_1") (pintype "passive"))
      (node (ref "R34") (pin "2") (pinfunction "2_2") (pintype "passive"))
      (node (ref "U14") (pin "5") (pinfunction "IN+_5") (pintype "input"))
    )
    (net (code "43") (name "Net-(U14B-IN-)") (class "Default")
      (node (ref "C57") (pin "2") (pinfunction "2_2") (pintype "passive"))
      (node (ref "C59") (pin "1") (pinfunction "1_1") (pintype "passive"))
      (node (ref "R30") (pin "2") (pinfunction "2_2") (pintype "passive"))
      (node (ref "R31") (pin "2") (pinfunction "2_2") (pintype "passive"))
      (node (ref "U14") (pin "6") (pinfunction "IN-_6") (pintype "input"))
    )
    (net (code "44") (name "Net-(U14B-OUT)") (class "Default")
      (node (ref "C61") (pin "2") (pinfunction "2_2") (pintype "passive"))
      (node (ref "R34") (pin "1") (pinfunction "1_1") (pintype "passive"))
      (node (ref "U14") (pin "7") (pinfunction "OUT_7") (pintype "output"))
      (node (ref "U15") (pin "3") (pinfunction "+IN_3") (pintype "input"))
    )
    (net (code "45") (name "Net-(U15-REF)") (class "Default")
      (node (ref "R38") (pin "2") (pinfunction "2_2") (pintype "passive"))
      (node (ref "TP8") (pin "P$1") (pinfunction "P$1_P$1") (pintype "bidirectional"))
      (node (ref "U15") (pin "1") (pinfunction "REF_1") (pintype "passive"))
      (node (ref "U16") (pin "6") (pinfunction "OUT_6") (pintype "output"))
    )
    (net (code "46") (name "Net-(U16-IN-)") (class "Default")
      (node (ref "R38") (pin "1") (pinfunction "1_1") (pintype "passive"))
      (node (ref "R39") (pin "1") (pinfunction "1_1") (pintype "passive"))
      (node (ref "U16") (pin "2") (pinfunction "IN-_2") (pintype "input"))
    )
    (net (code "47") (name "V+") (class "Default")
      (node (ref "C25") (pin "1") (pinfunction "1_1") (pintype "passive"))
      (node (ref "C26") (pin "1") (pinfunction "1_1") (pintype "passive"))
      (node (ref "C29") (pin "1") (pinfunction "1_1") (pintype "passive"))
      (node (ref "C31") (pin "1") (pinfunction "1_1") (pintype "passive"))
      (node (ref "C39") (pin "1") (pinfunction "1_1") (pintype "passive"))
      (node (ref "C41") (pin "1") (pinfunction "1_1") (pintype "passive"))
      (node (ref "C42") (pin "1") (pinfunction "1_1") (pintype "passive"))
      (node (ref "C45") (pin "1") (pinfunction "1_1") (pintype "passive"))
      (node (ref "C47") (pin "1") (pinfunction "1_1") (pintype "passive"))
      (node (ref "C49") (pin "1") (pinfunction "1_1") (pintype "passive"))
      (node (ref "C5") (pin "1") (pinfunction "1_1") (pintype "passive"))
      (node (ref "C50") (pin "1") (pinfunction "1_1") (pintype "passive"))
      (node (ref "C53") (pin "1") (pinfunction "1_1") (pintype "passive"))
      (node (ref "C55") (pin "1") (pinfunction "1_1") (pintype "passive"))
      (node (ref "C63") (pin "1") (pinfunction "1_1") (pintype "passive"))
      (node (ref "C7") (pin "1") (pinfunction "1_1") (pintype "passive"))
      (node (ref "C8") (pin "1") (pinfunction "1_1") (pintype "passive"))
      (node (ref "D1") (pin "C") (pinfunction "C_C") (pintype "passive"))
      (node (ref "D5") (pin "C") (pinfunction "C_C") (pintype "passive"))
      (node (ref "D7") (pin "C") (pinfunction "C_C") (pintype "passive"))
      (node (ref "Q1") (pin "C") (pinfunction "C_C") (pintype "passive"))
      (node (ref "Q5") (pin "C") (pinfunction "C_C") (pintype "passive"))
      (node (ref "Q7") (pin "C") (pinfunction "C_C") (pintype "passive"))
      (node (ref "U1") (pin "8") (pinfunction "V+_8") (pintype "power_in"))
      (node (ref "U10") (pin "8") (pinfunction "V+_8") (pintype "power_in"))
      (node (ref "U11") (pin "7") (pinfunction "V+_7") (pintype "power_in"))
      (node (ref "U12") (pin "7") (pinfunction "+VS_7") (pintype "input"))
      (node (ref "U13") (pin "7") (pinfunction "V+_7") (pintype "power_in"))
      (node (ref "U14") (pin "8") (pinfunction "V+_8") (pintype "power_in"))
      (node (ref "U15") (pin "7") (pinfunction "V+_7") (pintype "power_in"))
      (node (ref "U16") (pin "7") (pinfunction "+VS_7") (pintype "input"))
      (node (ref "U2") (pin "7") (pinfunction "V+_7") (pintype "power_in"))
      (node (ref "U3") (pin "7") (pinfunction "V+_7") (pintype "power_in"))
      (node (ref "U4") (pin "7") (pinfunction "+VS_7") (pintype "input"))
      (node (ref "U9") (pin "7") (pinfunction "V+_7") (pintype "power_in"))
      (node (ref "X12") (pin "2") (pinfunction "S_2") (pintype "passive"))
      (node (ref "X16") (pin "2") (pinfunction "S_2") (pintype "passive"))
      (node (ref "X5") (pin "1") (pinfunction "S_1") (pintype "passive"))
      (node (ref "X6") (pin "2") (pinfunction "S_2") (pintype "passive"))
      (node (ref "X7") (pin "1") (pinfunction "S_1") (pintype "passive"))
    )
    (net (code "48") (name "V-") (class "Default")
      (node (ref "C24") (pin "2") (pinfunction "2_2") (pintype "passive"))
      (node (ref "C27") (pin "2") (pinfunction "2_2") (pintype "passive"))
      (node (ref "C28") (pin "2") (pinfunction "2_2") (pintype "passive"))
      (node (ref "C30") (pin "2") (pinfunction "2_2") (pintype "passive"))
      (node (ref "C32") (pin "2") (pinfunction "2_2") (pintype "passive"))
      (node (ref "C40") (pin "2") (pinfunction "2_2") (pintype "passive"))
      (node (ref "C43") (pin "2") (pinfunction "2_2") (pintype "passive"))
      (node (ref "C44") (pin "2") (pinfunction "2_2") (pintype "passive"))
      (node (ref "C46") (pin "2") (pinfunction "2_2") (pintype "passive"))
      (node (ref "C48") (pin "2") (pinfunction "2_2") (pintype "passive"))
      (node (ref "C51") (pin "2") (pinfunction "2_2") (pintype "passive"))
      (node (ref "C52") (pin "2") (pinfunction "2_2") (pintype "passive"))
      (node (ref "C54") (pin "2") (pinfunction "2_2") (pintype "passive"))
      (node (ref "C56") (pin "2") (pinfunction "2_2") (pintype "passive"))
      (node (ref "C6") (pin "2") (pinfunction "2_2") (pintype "passive"))
      (node (ref "C64") (pin "2") (pinfunction "2_2") (pintype "passive"))
      (node (ref "C9") (pin "2") (pinfunction "2_2") (pintype "passive"))
      (node (ref "D3") (pin "A") (pinfunction "A_A") (pintype "passive"))
      (node (ref "D6") (pin "A") (pinfunction "A_A") (pintype "passive"))
      (node (ref "D8") (pin "A") (pinfunction "A_A") (pintype "passive"))
      (node (ref "Q2") (pin "C") (pinfunction "C_C") (pintype "passive"))
      (node (ref "Q6") (pin "C") (pinfunction "C_C") (pintype "passive"))
      (node (ref "Q8") (pin "C") (pinfunction "C_C") (pintype "passive"))
      (node (ref "R24") (pin "2") (pinfunction "2_2") (pintype "passive"))
      (node (ref "R35") (pin "2") (pinfunction "2_2") (pintype "passive"))
      (node (ref "R9") (pin "2") (pinfunction "2_2") (pintype "passive"))
      (node (ref "U1") (pin "4") (pinfunction "V-_4") (pintype "power_in"))
      (node (ref "U10") (pin "4") (pinfunction "V-_4") (pintype "power_in"))
      (node (ref "U11") (pin "4") (pinfunction "V-_4") (pintype "power_in"))
      (node (ref "U12") (pin "4") (pinfunction "-VS_4") (pintype "input"))
      (node (ref "U13") (pin "4") (pinfunction "V-_4") (pintype "power_in"))
      (node (ref "U14") (pin "4") (pinfunction "V-_4") (pintype "power_in"))
      (node (ref "U15") (pin "4") (pinfunction "V-_4") (pintype "power_in"))
      (node (ref "U16") (pin "4") (pinfunction "-VS_4") (pintype "input"))
      (node (ref "U2") (pin "4") (pinfunction "V-_4") (pintype "power_in"))
      (node (ref "U3") (pin "4") (pinfunction "V-_4") (pintype "power_in"))
      (node (ref "U4") (pin "4") (pinfunction "-VS_4") (pintype "input"))
      (node (ref "U9") (pin "4") (pinfunction "V-_4") (pintype "power_in"))
      (node (ref "X11") (pin "2") (pinfunction "S_2") (pintype "passive"))
      (node (ref "X15") (pin "2") (pinfunction "S_2") (pintype "passive"))
      (node (ref "X4") (pin "2") (pinfunction "S_2") (pintype "passive"))
      (node (ref "X5") (pin "3") (pinfunction "S_3") (pintype "passive"))
      (node (ref "X7") (pin "3") (pinfunction "S_3") (pintype "passive"))
    )
    (net (code "49") (name "unconnected-(U2-NC-Pad8)") (class "Default")
      (node (ref "U2") (pin "8") (pinfunction "NC_8") (pintype "no_connect"))
    )
    (net (code "50") (name "unconnected-(U4-OFF-Pad8)") (class "Default")
      (node (ref "U4") (pin "8") (pinfunction "OFF_8") (pintype "passive"))
    )
    (net (code "51") (name "unconnected-(U11-NC-Pad8)") (class "Default")
      (node (ref "U11") (pin "8") (pinfunction "NC_8") (pintype "no_connect"))
    )
    (net (code "52") (name "unconnected-(U12-OFF-Pad8)") (class "Default")
      (node (ref "U12") (pin "8") (pinfunction "OFF_8") (pintype "passive"))
    )
    (net (code "53") (name "unconnected-(U15-NC-Pad8)") (class "Default")
      (node (ref "U15") (pin "8") (pinfunction "NC_8") (pintype "no_connect"))
    )
    (net (code "54") (name "unconnected-(U16-OFF-Pad8)") (class "Default")
      (node (ref "U16") (pin "8") (pinfunction "OFF_8") (pintype "passive"))
    )
  )
)
